# v001.net
KiCad netlist of a schematic drawn in EAGLE
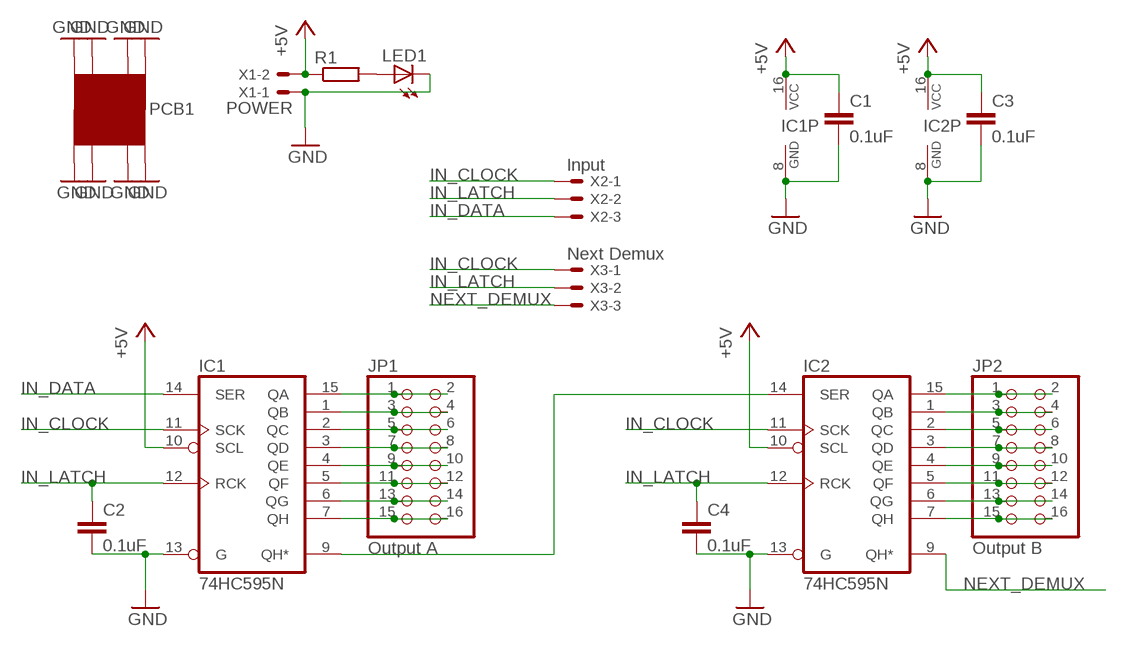
[diagram p0: schematic, sheet 1]

(export (version "E")
  (design (tool "Eeschema 10.0.6"))
  (components
    (comp (ref "C1")
      (value "0.1uF")
      (footprint "eagle-import:C050-024X044")
      (libsource (lib "eagle-import") (part "C-EU050-024X044"))
    )
    (comp (ref "C2")
      (value "0.1uF")
      (footprint "eagle-import:C050-024X044")
      (libsource (lib "eagle-import") (part "C-EU050-024X044"))
    )
    (comp (ref "C3")
      (value "0.1uF")
      (footprint "eagle-import:C050-024X044")
      (libsource (lib "eagle-import") (part "C-EU050-024X044"))
    )
    (comp (ref "C4")
      (value "0.1uF")
      (footprint "eagle-import:C050-024X044")
      (libsource (lib "eagle-import") (part "C-EU050-024X044"))
    )
    (comp (ref "IC1")
      (value "74HC595N")
      (footprint "eagle-import:DIL16")
      (libsource (lib "eagle-import") (part "74595NHC"))
    )
    (comp (ref "IC2")
      (value "74HC595N")
      (footprint "eagle-import:DIL16")
      (libsource (lib "eagle-import") (part "74595NHC"))
    )
    (comp (ref "JP1")
      (value "Output A")
      (footprint "eagle-import:2X08")
      (libsource (lib "eagle-import") (part "PINHD-2X8"))
    )
    (comp (ref "JP2")
      (value "Output B")
      (footprint "eagle-import:2X08")
      (libsource (lib "eagle-import") (part "PINHD-2X8"))
    )
    (comp (ref "LED1")
      (value "LED3MM")
      (footprint "eagle-import:LED3MM")
      (libsource (lib "eagle-import") (part "LED3MM"))
    )
    (comp (ref "PCB1")
      (value "PCB05X05")
      (footprint "eagle-import:PCB_05X05")
      (libsource (lib "eagle-import") (part "PCB05X05"))
    )
    (comp (ref "R1")
      (value "R-EU_0207/2V")
      (footprint "eagle-import:0207_2V")
      (libsource (lib "eagle-import") (part "R-EU_0207/2V"))
    )
    (comp (ref "X1")
      (value "POWER")
      (footprint "eagle-import:22-23-2021")
      (fields (field (name "MF") "MOLEX") (field (name "MPN") "22-23-2021"))
      (libsource (lib "eagle-import") (part "22-23-2021"))
    )
    (comp (ref "X2")
      (value "Input")
      (footprint "eagle-import:22-23-2031")
      (fields (field (name "MF") "MOLEX") (field (name "MPN") "22-23-2031"))
      (libsource (lib "eagle-import") (part "22-23-2031"))
    )
    (comp (ref "X3")
      (value "Next Demux")
      (footprint "eagle-import:22-23-2031")
      (fields (field (name "MF") "MOLEX") (field (name "MPN") "22-23-2031"))
      (libsource (lib "eagle-import") (part "22-23-2031"))
    )
  )
  (nets
    (net (code "1") (name "+5V") (class "Default")
      (node (ref "C1") (pin "1") (pinfunction "1_1") (pintype "passive"))
      (node (ref "C3") (pin "1") (pinfunction "1_1") (pintype "passive"))
      (node (ref "IC1") (pin "10") (pinfunction "SCL_10") (pintype "input"))
      (node (ref "IC1") (pin "16") (pinfunction "VCC_16") (pintype "power_in"))
      (node (ref "IC2") (pin "10") (pinfunction "SCL_10") (pintype "input"))
      (node (ref "IC2") (pin "16") (pinfunction "VCC_16") (pintype "power_in"))
      (node (ref "R1") (pin "1") (pinfunction "1_1") (pintype "passive"))
      (node (ref "X1") (pin "2") (pinfunction "S_2") (pintype "passive"))
    )
    (net (code "2") (name "/IN_CLOCK") (class "Default")
      (node (ref "IC1") (pin "11") (pinfunction "SCK_11") (pintype "input"))
      (node (ref "IC2") (pin "11") (pinfunction "SCK_11") (pintype "input"))
      (node (ref "X2") (pin "1") (pinfunction "S_1") (pintype "passive"))
      (node (ref "X3") (pin "1") (pinfunction "S_1") (pintype "passive"))
    )
    (net (code "3") (name "/IN_DATA") (class "Default")
      (node (ref "IC1") (pin "14") (pinfunction "SER_14") (pintype "input"))
      (node (ref "X2") (pin "3") (pinfunction "S_3") (pintype "passive"))
    )
    (net (code "4") (name "/IN_LATCH") (class "Default")
      (node (ref "C2") (pin "1") (pinfunction "1_1") (pintype "passive"))
      (node (ref "C4") (pin "1") (pinfunction "1_1") (pintype "passive"))
      (node (ref "IC1") (pin "12") (pinfunction "RCK_12") (pintype "input"))
      (node (ref "IC2") (pin "12") (pinfunction "RCK_12") (pintype "input"))
      (node (ref "X2") (pin "2") (pinfunction "S_2") (pintype "passive"))
      (node (ref "X3") (pin "2") (pinfunction "S_2") (pintype "passive"))
    )
    (net (code "5") (name "/NEXT_DEMUX") (class "Default")
      (node (ref "IC2") (pin "9") (pinfunction "QH*_9") (pintype "tri_state"))
      (node (ref "X3") (pin "3") (pinfunction "S_3") (pintype "passive"))
    )
    (net (code "6") (name "GND") (class "Default")
      (node (ref "C1") (pin "2") (pinfunction "2_2") (pintype "passive"))
      (node (ref "C2") (pin "2") (pinfunction "2_2") (pintype "passive"))
      (node (ref "C3") (pin "2") (pinfunction "2_2") (pintype "passive"))
      (node (ref "C4") (pin "2") (pinfunction "2_2") (pintype "passive"))
      (node (ref "IC1") (pin "13") (pinfunction "G_13") (pintype "input"))
      (node (ref "IC1") (pin "8") (pinfunction "GND_8") (pintype "power_in"))
      (node (ref "IC2") (pin "13") (pinfunction "G_13") (pintype "input"))
      (node (ref "IC2") (pin "8") (pinfunction "GND_8") (pintype "power_in"))
      (node (ref "LED1") (pin "K") (pinfunction "C_K") (pintype "passive"))
      (node (ref "PCB1") (pin "GND@1") (pinfunction "GND_GND@1") (pintype "bidirectional"))
      (node (ref "PCB1") (pin "GND@2") (pinfunction "GND_GND@2") (pintype "bidirectional"))
      (node (ref "PCB1") (pin "GND@3") (pinfunction "GND_GND@3") (pintype "bidirectional"))
      (node (ref "PCB1") (pin "GND@4") (pinfunction "GND_GND@4") (pintype "bidirectional"))
      (node (ref "PCB1") (pin "GND@5") (pinfunction "GND_GND@5") (pintype "bidirectional"))
      (node (ref "PCB1") (pin "GND@6") (pinfunction "GND_GND@6") (pintype "bidirectional"))
      (node (ref "PCB1") (pin "GND@7") (pinfunction "GND_GND@7") (pintype "bidirectional"))
      (node (ref "PCB1") (pin "GND@8") (pinfunction "GND_GND@8") (pintype "bidirectional"))
      (node (ref "X1") (pin "1") (pinfunction "S_1") (pintype "passive"))
    )
    (net (code "7") (name "Net-(IC1A-QA)") (class "Default")
      (node (ref "IC1") (pin "15") (pinfunction "QA_15") (pintype "tri_state"))
      (node (ref "JP1") (pin "1") (pinfunction "1_1") (pintype "passive"))
      (node (ref "JP1") (pin "2") (pinfunction "2_2") (pintype "passive"))
    )
    (net (code "8") (name "Net-(IC1A-QB)") (class "Default")
      (node (ref "IC1") (pin "1") (pinfunction "QB_1") (pintype "tri_state"))
      (node (ref "JP1") (pin "3") (pinfunction "3_3") (pintype "passive"))
      (node (ref "JP1") (pin "4") (pinfunction "4_4") (pintype "passive"))
    )
    (net (code "9") (name "Net-(IC1A-QC)") (class "Default")
      (node (ref "IC1") (pin "2") (pinfunction "QC_2") (pintype "tri_state"))
      (node (ref "JP1") (pin "5") (pinfunction "5_5") (pintype "passive"))
      (node (ref "JP1") (pin "6") (pinfunction "6_6") (pintype "passive"))
    )
    (net (code "10") (name "Net-(IC1A-QD)") (class "Default")
      (node (ref "IC1") (pin "3") (pinfunction "QD_3") (pintype "tri_state"))
      (node (ref "JP1") (pin "7") (pinfunction "7_7") (pintype "passive"))
      (node (ref "JP1") (pin "8") (pinfunction "8_8") (pintype "passive"))
    )
    (net (code "11") (name "Net-(IC1A-QE)") (class "Default")
      (node (ref "IC1") (pin "4") (pinfunction "QE_4") (pintype "tri_state"))
      (node (ref "JP1") (pin "10") (pinfunction "10_10") (pintype "passive"))
      (node (ref "JP1") (pin "9") (pinfunction "9_9") (pintype "passive"))
    )
    (net (code "12") (name "Net-(IC1A-QF)") (class "Default")
      (node (ref "IC1") (pin "5") (pinfunction "QF_5") (pintype "tri_state"))
      (node (ref "JP1") (pin "11") (pinfunction "11_11") (pintype "passive"))
      (node (ref "JP1") (pin "12") (pinfunction "12_12") (pintype "passive"))
    )
    (net (code "13") (name "Net-(IC1A-QG)") (class "Default")
      (node (ref "IC1") (pin "6") (pinfunction "QG_6") (pintype "tri_state"))
      (node (ref "JP1") (pin "13") (pinfunction "13_13") (pintype "passive"))
      (node (ref "JP1") (pin "14") (pinfunction "14_14") (pintype "passive"))
    )
    (net (code "14") (name "Net-(IC1A-QH)") (class "Default")
      (node (ref "IC1") (pin "7") (pinfunction "QH_7") (pintype "tri_state"))
      (node (ref "JP1") (pin "15") (pinfunction "15_15") (pintype "passive"))
      (node (ref "JP1") (pin "16") (pinfunction "16_16") (pintype "passive"))
    )
    (net (code "15") (name "Net-(IC1A-QH*)") (class "Default")
      (node (ref "IC1") (pin "9") (pinfunction "QH*_9") (pintype "tri_state"))
      (node (ref "IC2") (pin "14") (pinfunction "SER_14") (pintype "input"))
    )
    (net (code "16") (name "Net-(IC2A-QA)") (class "Default")
      (node (ref "IC2") (pin "15") (pinfunction "QA_15") (pintype "tri_state"))
      (node (ref "JP2") (pin "1") (pinfunction "1_1") (pintype "passive"))
      (node (ref "JP2") (pin "2") (pinfunction "2_2") (pintype "passive"))
    )
    (net (code "17") (name "Net-(IC2A-QB)") (class "Default")
      (node (ref "IC2") (pin "1") (pinfunction "QB_1") (pintype "tri_state"))
      (node (ref "JP2") (pin "3") (pinfunction "3_3") (pintype "passive"))
      (node (ref "JP2") (pin "4") (pinfunction "4_4") (pintype "passive"))
    )
    (net (code "18") (name "Net-(IC2A-QC)") (class "Default")
      (node (ref "IC2") (pin "2") (pinfunction "QC_2") (pintype "tri_state"))
      (node (ref "JP2") (pin "5") (pinfunction "5_5") (pintype "passive"))
      (node (ref "JP2") (pin "6") (pinfunction "6_6") (pintype "passive"))
    )
    (net (code "19") (name "Net-(IC2A-QD)") (class "Default")
      (node (ref "IC2") (pin "3") (pinfunction "QD_3") (pintype "tri_state"))
      (node (ref "JP2") (pin "7") (pinfunction "7_7") (pintype "passive"))
      (node (ref "JP2") (pin "8") (pinfunction "8_8") (pintype "passive"))
    )
    (net (code "20") (name "Net-(IC2A-QE)") (class "Default")
      (node (ref "IC2") (pin "4") (pinfunction "QE_4") (pintype "tri_state"))
      (node (ref "JP2") (pin "10") (pinfunction "10_10") (pintype "passive"))
      (node (ref "JP2") (pin "9") (pinfunction "9_9") (pintype "passive"))
    )
    (net (code "21") (name "Net-(IC2A-QF)") (class "Default")
      (node (ref "IC2") (pin "5") (pinfunction "QF_5") (pintype "tri_state"))
      (node (ref "JP2") (pin "11") (pinfunction "11_11") (pintype "passive"))
      (node (ref "JP2") (pin "12") (pinfunction "12_12") (pintype "passive"))
    )
    (net (code "22") (name "Net-(IC2A-QG)") (class "Default")
      (node (ref "IC2") (pin "6") (pinfunction "QG_6") (pintype "tri_state"))
      (node (ref "JP2") (pin "13") (pinfunction "13_13") (pintype "passive"))
      (node (ref "JP2") (pin "14") (pinfunction "14_14") (pintype "passive"))
    )
    (net (code "23") (name "Net-(IC2A-QH)") (class "Default")
      (node (ref "IC2") (pin "7") (pinfunction "QH_7") (pintype "tri_state"))
      (node (ref "JP2") (pin "15") (pinfunction "15_15") (pintype "passive"))
      (node (ref "JP2") (pin "16") (pinfunction "16_16") (pintype "passive"))
    )
    (net (code "24") (name "Net-(LED1-PadA)") (class "Default")
      (node (ref "LED1") (pin "A") (pinfunction "A_A") (pintype "passive"))
      (node (ref "R1") (pin "2") (pinfunction "2_2") (pintype "passive"))
    )
  )
)
